# msp_mcu.net
KiCad netlist of a schematic drawn in Altium Designer
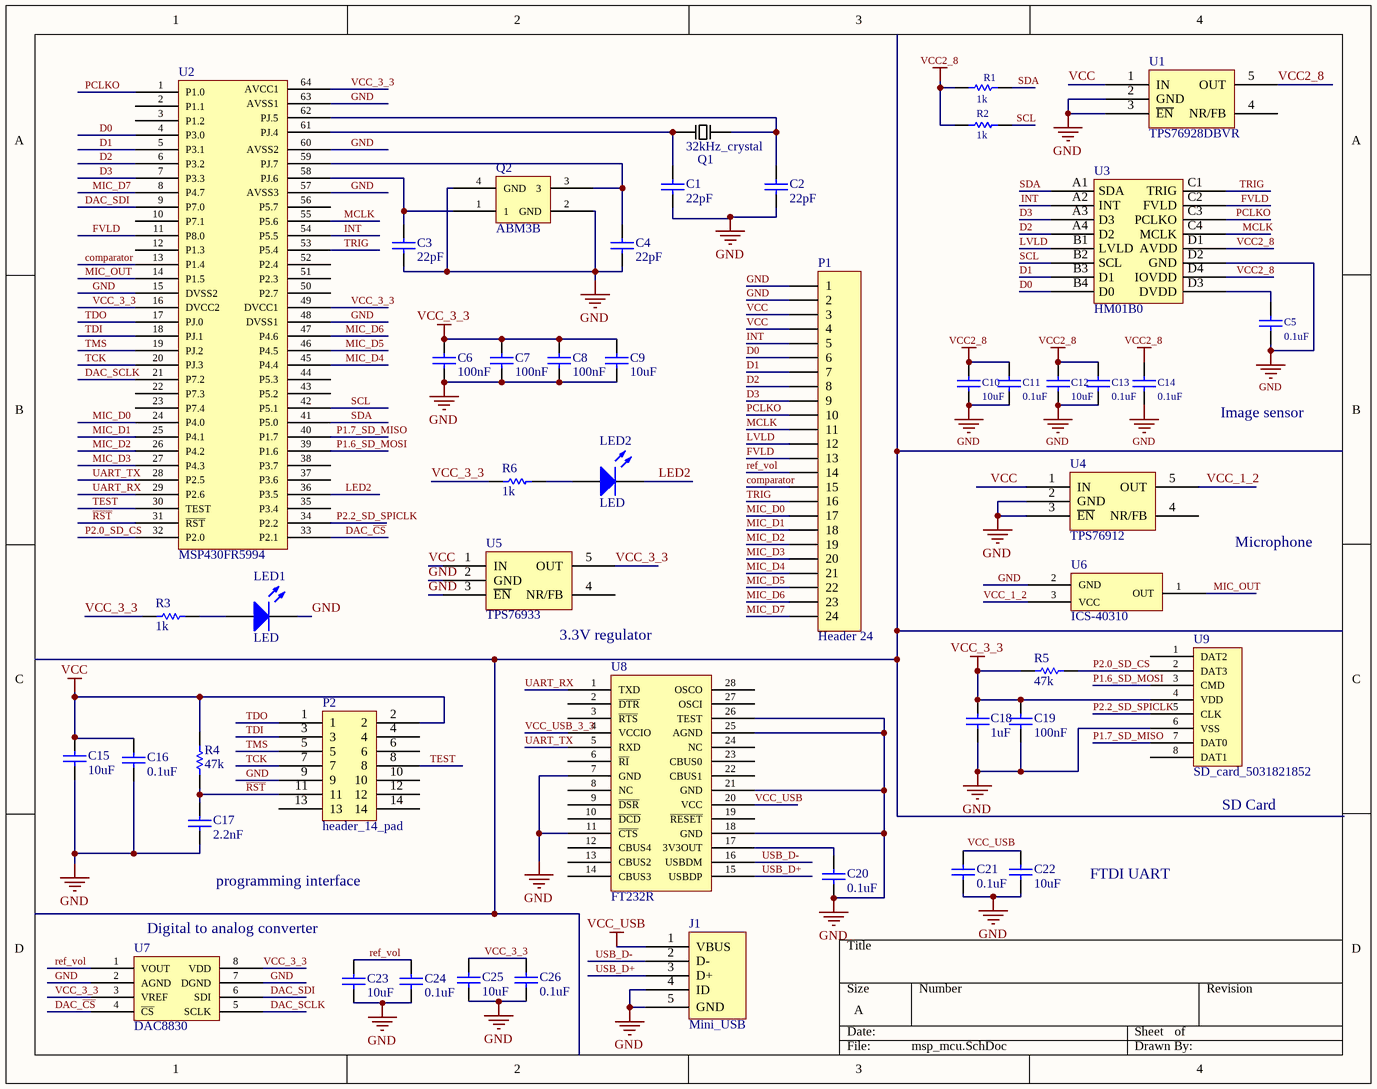
[diagram p0: msp_mcu.SchDoc]

(export (version "E")
  (design (tool "Eeschema 10.0.6"))
  (components
    (comp (ref "C1")
      (value "22pF")
      (footprint "0603")
      (description "Ceramic Capacitor (Surface Mount)")
      (fields (field (name "MANUFACTURER") "Generic Ceramic Chip Cap (TBD)") (field (name "Comment") "Cap"))
      (libsource (lib "wisp") (part "Cap"))
    )
    (comp (ref "C2")
      (value "22pF")
      (footprint "0603")
      (description "Ceramic Capacitor (Surface Mount)")
      (fields (field (name "MANUFACTURER") "Generic Ceramic Chip Cap (TBD)") (field (name "Comment") "Cap"))
      (libsource (lib "wisp") (part "Cap"))
    )
    (comp (ref "C3")
      (value "22pF")
      (footprint "0603")
      (description "Ceramic Capacitor (Surface Mount)")
      (fields (field (name "MANUFACTURER") "Generic Ceramic Chip Cap (TBD)") (field (name "Comment") "Cap"))
      (libsource (lib "wisp") (part "Cap"))
    )
    (comp (ref "C4")
      (value "22pF")
      (footprint "0603")
      (description "Ceramic Capacitor (Surface Mount)")
      (fields (field (name "MANUFACTURER") "Generic Ceramic Chip Cap (TBD)") (field (name "Comment") "Cap"))
      (libsource (lib "wisp") (part "Cap"))
    )
    (comp (ref "C5")
      (value "0.1uF")
      (footprint "0603")
      (description "Ceramic Capacitor (Surface Mount)")
      (fields (field (name "MANUFACTURER") "Generic Ceramic Chip Cap (TBD)") (field (name "Comment") "Cap"))
      (libsource (lib "wisp") (part "Cap"))
    )
    (comp (ref "C6")
      (value "100nF")
      (footprint "0603")
      (description "Ceramic Capacitor (Surface Mount)")
      (fields (field (name "MANUFACTURER") "Generic Ceramic Chip Cap (TBD)") (field (name "Comment") "Cap"))
      (libsource (lib "wisp") (part "Cap"))
    )
    (comp (ref "C7")
      (value "100nF")
      (footprint "0603")
      (description "Ceramic Capacitor (Surface Mount)")
      (fields (field (name "MANUFACTURER") "Generic Ceramic Chip Cap (TBD)") (field (name "Comment") "Cap"))
      (libsource (lib "wisp") (part "Cap"))
    )
    (comp (ref "C8")
      (value "100nF")
      (footprint "0603")
      (description "Ceramic Capacitor (Surface Mount)")
      (fields (field (name "MANUFACTURER") "Generic Ceramic Chip Cap (TBD)") (field (name "Comment") "Cap"))
      (libsource (lib "wisp") (part "Cap"))
    )
    (comp (ref "C9")
      (value "10uF")
      (footprint "0603")
      (description "Ceramic Capacitor (Surface Mount)")
      (fields (field (name "MANUFACTURER") "Generic Ceramic Chip Cap (TBD)") (field (name "Comment") "Cap"))
      (libsource (lib "wisp") (part "Cap"))
    )
    (comp (ref "C10")
      (value "10uF")
      (footprint "0603")
      (description "Ceramic Capacitor (Surface Mount)")
      (fields (field (name "MANUFACTURER") "Generic Ceramic Chip Cap (TBD)") (field (name "Comment") "Cap"))
      (libsource (lib "wisp") (part "Cap"))
    )
    (comp (ref "C11")
      (value "0.1uF")
      (footprint "0603")
      (description "Ceramic Capacitor (Surface Mount)")
      (fields (field (name "MANUFACTURER") "Generic Ceramic Chip Cap (TBD)") (field (name "Comment") "Cap"))
      (libsource (lib "wisp") (part "Cap"))
    )
    (comp (ref "C12")
      (value "10uF")
      (footprint "0603")
      (description "Ceramic Capacitor (Surface Mount)")
      (fields (field (name "MANUFACTURER") "Generic Ceramic Chip Cap (TBD)") (field (name "Comment") "Cap"))
      (libsource (lib "wisp") (part "Cap"))
    )
    (comp (ref "C13")
      (value "0.1uF")
      (footprint "0603")
      (description "Ceramic Capacitor (Surface Mount)")
      (fields (field (name "MANUFACTURER") "Generic Ceramic Chip Cap (TBD)") (field (name "Comment") "Cap"))
      (libsource (lib "wisp") (part "Cap"))
    )
    (comp (ref "C14")
      (value "0.1uF")
      (footprint "0603")
      (description "Ceramic Capacitor (Surface Mount)")
      (fields (field (name "MANUFACTURER") "Generic Ceramic Chip Cap (TBD)") (field (name "Comment") "Cap"))
      (libsource (lib "wisp") (part "Cap"))
    )
    (comp (ref "C15")
      (value "10uF")
      (footprint "0603")
      (description "Ceramic Capacitor (Surface Mount)")
      (fields (field (name "MANUFACTURER") "Generic Ceramic Chip Cap (TBD)") (field (name "Comment") "Cap"))
      (libsource (lib "wisp") (part "Cap"))
    )
    (comp (ref "C16")
      (value "0.1uF")
      (footprint "0603")
      (description "Ceramic Capacitor (Surface Mount)")
      (fields (field (name "MANUFACTURER") "Generic Ceramic Chip Cap (TBD)") (field (name "Comment") "Cap"))
      (libsource (lib "wisp") (part "Cap"))
    )
    (comp (ref "C17")
      (value "2.2nF")
      (footprint "0603")
      (description "Ceramic Capacitor (Surface Mount)")
      (fields (field (name "MANUFACTURER") "Generic Ceramic Chip Cap (TBD)") (field (name "Comment") "Cap"))
      (libsource (lib "wisp") (part "Cap"))
    )
    (comp (ref "C18")
      (value "1uF")
      (footprint "0603")
      (description "Ceramic Capacitor (Surface Mount)")
      (fields (field (name "MANUFACTURER") "Generic Ceramic Chip Cap (TBD)") (field (name "Comment") "Cap"))
      (libsource (lib "wisp") (part "Cap"))
    )
    (comp (ref "C19")
      (value "100nF")
      (footprint "0603")
      (description "Ceramic Capacitor (Surface Mount)")
      (fields (field (name "MANUFACTURER") "Generic Ceramic Chip Cap (TBD)") (field (name "Comment") "Cap"))
      (libsource (lib "wisp") (part "Cap"))
    )
    (comp (ref "C20")
      (value "0.1uF")
      (footprint "0603")
      (description "Ceramic Capacitor (Surface Mount)")
      (fields (field (name "MANUFACTURER") "Generic Ceramic Chip Cap (TBD)") (field (name "Comment") "Cap"))
      (libsource (lib "wisp") (part "Cap"))
    )
    (comp (ref "C21")
      (value "0.1uF")
      (footprint "0603")
      (description "Ceramic Capacitor (Surface Mount)")
      (fields (field (name "MANUFACTURER") "Generic Ceramic Chip Cap (TBD)") (field (name "Comment") "Cap"))
      (libsource (lib "wisp") (part "Cap"))
    )
    (comp (ref "C22")
      (value "10uF")
      (footprint "0603")
      (description "Ceramic Capacitor (Surface Mount)")
      (fields (field (name "MANUFACTURER") "Generic Ceramic Chip Cap (TBD)") (field (name "Comment") "Cap"))
      (libsource (lib "wisp") (part "Cap"))
    )
    (comp (ref "C23")
      (value "10uF")
      (footprint "0603")
      (description "Ceramic Capacitor (Surface Mount)")
      (fields (field (name "MANUFACTURER") "Generic Ceramic Chip Cap (TBD)") (field (name "Comment") "Cap"))
      (libsource (lib "wisp") (part "Cap"))
    )
    (comp (ref "C24")
      (value "0.1uF")
      (footprint "0603")
      (description "Ceramic Capacitor (Surface Mount)")
      (fields (field (name "MANUFACTURER") "Generic Ceramic Chip Cap (TBD)") (field (name "Comment") "Cap"))
      (libsource (lib "wisp") (part "Cap"))
    )
    (comp (ref "C25")
      (value "10uF")
      (footprint "0603")
      (description "Ceramic Capacitor (Surface Mount)")
      (fields (field (name "MANUFACTURER") "Generic Ceramic Chip Cap (TBD)") (field (name "Comment") "Cap"))
      (libsource (lib "wisp") (part "Cap"))
    )
    (comp (ref "C26")
      (value "0.1uF")
      (footprint "0603")
      (description "Ceramic Capacitor (Surface Mount)")
      (fields (field (name "MANUFACTURER") "Generic Ceramic Chip Cap (TBD)") (field (name "Comment") "Cap"))
      (libsource (lib "wisp") (part "Cap"))
    )
    (comp (ref "J1")
      (value "Mini_USB")
      (footprint "Mini_USB")
      (libsource (lib "pengyulib") (part "Mini_USB"))
    )
    (comp (ref "LED1") (value "LED") (libsource (lib "pengyulib") (part "LED")))
    (comp (ref "LED2") (value "LED") (libsource (lib "pengyulib") (part "LED")))
    (comp (ref "P1")
      (value "Header 24")
      (footprint "HDR1X24")
      (description "Header, 24-Pin")
      (fields (field (name "PUBLISHER") "Altium Limited"))
      (libsource (lib "Miscellaneous Connectors") (part "Header 24"))
    )
    (comp (ref "P2")
      (value "header_14_pad")
      (footprint "header_14_pad")
      (libsource (lib "pengyulib") (part "header_14_pad"))
    )
    (comp (ref "Q1")
      (value "32kHz_crystal")
      (footprint "32kHz_crystal")
      (libsource (lib "pengyulib") (part "32kHz_crystal"))
    )
    (comp (ref "Q2") (value "ABM3B") (footprint "ABM3B") (libsource (lib "pengyulib") (part "ABM3B")))
    (comp (ref "R1")
      (value "1k")
      (footprint "0603")
      (description "Chip Resistor (Surface Mount)")
      (fields (field (name "MANUFACTURER") "Generic Chip Res (TBD)") (field (name "Comment") "Res"))
      (libsource (lib "wisp") (part "Res"))
    )
    (comp (ref "R2")
      (value "1k")
      (footprint "0603")
      (description "Chip Resistor (Surface Mount)")
      (fields (field (name "MANUFACTURER") "Generic Chip Res (TBD)") (field (name "Comment") "Res"))
      (libsource (lib "wisp") (part "Res"))
    )
    (comp (ref "R3")
      (value "1k")
      (footprint "0603")
      (description "Chip Resistor (Surface Mount)")
      (fields (field (name "MANUFACTURER") "Generic Chip Res (TBD)") (field (name "Comment") "Res"))
      (libsource (lib "wisp") (part "Res"))
    )
    (comp (ref "R4")
      (value "47k")
      (footprint "0603")
      (description "Chip Resistor (Surface Mount)")
      (fields (field (name "MANUFACTURER") "Generic Chip Res (TBD)") (field (name "Comment") "Res"))
      (libsource (lib "wisp") (part "Res"))
    )
    (comp (ref "R5")
      (value "47k")
      (footprint "0603")
      (description "Chip Resistor (Surface Mount)")
      (fields (field (name "MANUFACTURER") "Generic Chip Res (TBD)") (field (name "Comment") "Res"))
      (libsource (lib "wisp") (part "Res"))
    )
    (comp (ref "R6")
      (value "1k")
      (footprint "0603")
      (description "Chip Resistor (Surface Mount)")
      (fields (field (name "MANUFACTURER") "Generic Chip Res (TBD)") (field (name "Comment") "Res"))
      (libsource (lib "wisp") (part "Res"))
    )
    (comp (ref "U1")
      (value "TPS76928DBVR")
      (footprint "TPS73633")
      (description "TPS73633")
      (libsource (lib "pengyulib") (part "TPS76928DBVR"))
    )
    (comp (ref "U2")
      (value "MSP430FR5994")
      (footprint "MSP430FR5994")
      (libsource (lib "pengyulib") (part "MSP430FR5994"))
    )
    (comp (ref "U3") (value "HM01B0") (footprint "HM01B0") (libsource (lib "pengyulib") (part "HM01B0")))
    (comp (ref "U4")
      (value "TPS76912")
      (footprint "TPS73633")
      (description "TPS73633")
      (libsource (lib "pengyulib") (part "TPS76912"))
    )
    (comp (ref "U5")
      (value "TPS76933")
      (footprint "TPS73633")
      (description "TPS73633")
      (libsource (lib "pengyulib") (part "TPS76933"))
    )
    (comp (ref "U6")
      (value "ICS-40310")
      (footprint "ICS-40310")
      (libsource (lib "pengyulib") (part "ICS-40310"))
    )
    (comp (ref "U7") (value "DAC8830") (footprint "DAC8830") (libsource (lib "pengyulib") (part "DAC8830")))
    (comp (ref "U8") (value "FT232R") (footprint "FT232R") (libsource (lib "pengyulib") (part "FT232R")))
    (comp (ref "U9")
      (value "SD_card_5031821852")
      (footprint "SD_card_5031821852")
      (libsource (lib "pengyulib") (part "SD_card_5031821852"))
    )
  )
  (nets
    (net (code "1") (name "/D0") (class "Default")
      (node (ref "P1") (pin "6") (pinfunction "6_6") (pintype "passive"))
      (node (ref "U2") (pin "4") (pinfunction "P3.0_4") (pintype "passive"))
      (node (ref "U3") (pin "B4") (pinfunction "D0_B4") (pintype "passive"))
    )
    (net (code "2") (name "/D1") (class "Default")
      (node (ref "P1") (pin "7") (pinfunction "7_7") (pintype "passive"))
      (node (ref "U2") (pin "5") (pinfunction "P3.1_5") (pintype "passive"))
      (node (ref "U3") (pin "B3") (pinfunction "D1_B3") (pintype "passive"))
    )
    (net (code "3") (name "/D2") (class "Default")
      (node (ref "P1") (pin "8") (pinfunction "8_8") (pintype "passive"))
      (node (ref "U2") (pin "6") (pinfunction "P3.2_6") (pintype "passive"))
      (node (ref "U3") (pin "A4") (pinfunction "D2_A4") (pintype "passive"))
    )
    (net (code "4") (name "/D3") (class "Default")
      (node (ref "P1") (pin "9") (pinfunction "9_9") (pintype "passive"))
      (node (ref "U2") (pin "7") (pinfunction "P3.3_7") (pintype "passive"))
      (node (ref "U3") (pin "A3") (pinfunction "D3_A3") (pintype "passive"))
    )
    (net (code "5") (name "/DAC_SCLK") (class "Default")
      (node (ref "U2") (pin "21") (pinfunction "P7.2_21") (pintype "passive"))
      (node (ref "U7") (pin "5") (pinfunction "SCLK_5") (pintype "passive"))
    )
    (net (code "6") (name "/DAC_SDI") (class "Default")
      (node (ref "U2") (pin "9") (pinfunction "P7.0_9") (pintype "passive"))
      (node (ref "U7") (pin "6") (pinfunction "SDI_6") (pintype "passive"))
    )
    (net (code "7") (name "/DAC_~{CS}") (class "Default")
      (node (ref "U2") (pin "33") (pinfunction "P2.1_33") (pintype "passive"))
      (node (ref "U7") (pin "4") (pinfunction "~{CS}_4") (pintype "passive"))
    )
    (net (code "8") (name "/FVLD") (class "Default")
      (node (ref "P1") (pin "13") (pinfunction "13_13") (pintype "passive"))
      (node (ref "U2") (pin "11") (pinfunction "P8.0_11") (pintype "passive"))
      (node (ref "U3") (pin "C2") (pinfunction "FVLD_C2") (pintype "passive"))
    )
    (net (code "9") (name "/INT") (class "Default")
      (node (ref "P1") (pin "5") (pinfunction "5_5") (pintype "passive"))
      (node (ref "U2") (pin "54") (pinfunction "P5.5_54") (pintype "passive"))
      (node (ref "U3") (pin "A2") (pinfunction "INT_A2") (pintype "passive"))
    )
    (net (code "10") (name "/LED2") (class "Default")
      (node (ref "LED2") (pin "2") (pinfunction "K_2") (pintype "passive"))
      (node (ref "U2") (pin "36") (pinfunction "P3.5_36") (pintype "passive"))
    )
    (net (code "11") (name "/LVLD") (class "Default")
      (node (ref "P1") (pin "12") (pinfunction "12_12") (pintype "passive"))
      (node (ref "U3") (pin "B1") (pinfunction "LVLD_B1") (pintype "passive"))
    )
    (net (code "12") (name "/MCLK") (class "Default")
      (node (ref "P1") (pin "11") (pinfunction "11_11") (pintype "passive"))
      (node (ref "U2") (pin "55") (pinfunction "P5.6_55") (pintype "passive"))
      (node (ref "U3") (pin "C4") (pinfunction "MCLK_C4") (pintype "passive"))
    )
    (net (code "13") (name "/MIC_D0") (class "Default")
      (node (ref "P1") (pin "17") (pinfunction "17_17") (pintype "passive"))
      (node (ref "U2") (pin "24") (pinfunction "P4.0_24") (pintype "passive"))
    )
    (net (code "14") (name "/MIC_D1") (class "Default")
      (node (ref "P1") (pin "18") (pinfunction "18_18") (pintype "passive"))
      (node (ref "U2") (pin "25") (pinfunction "P4.1_25") (pintype "passive"))
    )
    (net (code "15") (name "/MIC_D2") (class "Default")
      (node (ref "P1") (pin "19") (pinfunction "19_19") (pintype "passive"))
      (node (ref "U2") (pin "26") (pinfunction "P4.2_26") (pintype "passive"))
    )
    (net (code "16") (name "/MIC_D3") (class "Default")
      (node (ref "P1") (pin "20") (pinfunction "20_20") (pintype "passive"))
      (node (ref "U2") (pin "27") (pinfunction "P4.3_27") (pintype "passive"))
    )
    (net (code "17") (name "/MIC_D4") (class "Default")
      (node (ref "P1") (pin "21") (pinfunction "21_21") (pintype "passive"))
      (node (ref "U2") (pin "45") (pinfunction "P4.4_45") (pintype "passive"))
    )
    (net (code "18") (name "/MIC_D5") (class "Default")
      (node (ref "P1") (pin "22") (pinfunction "22_22") (pintype "passive"))
      (node (ref "U2") (pin "46") (pinfunction "P4.5_46") (pintype "passive"))
    )
    (net (code "19") (name "/MIC_D6") (class "Default")
      (node (ref "P1") (pin "23") (pinfunction "23_23") (pintype "passive"))
      (node (ref "U2") (pin "47") (pinfunction "P4.6_47") (pintype "passive"))
    )
    (net (code "20") (name "/MIC_D7") (class "Default")
      (node (ref "P1") (pin "24") (pinfunction "24_24") (pintype "passive"))
      (node (ref "U2") (pin "8") (pinfunction "P4.7_8") (pintype "passive"))
    )
    (net (code "21") (name "/MIC_OUT") (class "Default")
      (node (ref "U2") (pin "14") (pinfunction "P1.5_14") (pintype "passive"))
      (node (ref "U6") (pin "1") (pinfunction "OUT_1") (pintype "passive"))
    )
    (net (code "22") (name "/P1.6_SD_MOSI") (class "Default")
      (node (ref "U2") (pin "39") (pinfunction "P1.6_39") (pintype "passive"))
      (node (ref "U9") (pin "3") (pinfunction "CMD_3") (pintype "passive"))
    )
    (net (code "23") (name "/P1.7_SD_MISO") (class "Default")
      (node (ref "U2") (pin "40") (pinfunction "P1.7_40") (pintype "passive"))
      (node (ref "U9") (pin "7") (pinfunction "DAT0_7") (pintype "passive"))
    )
    (net (code "24") (name "/P2.0_SD_CS") (class "Default")
      (node (ref "R5") (pin "2") (pinfunction "2_2") (pintype "passive"))
      (node (ref "U2") (pin "32") (pinfunction "P2.0_32") (pintype "passive"))
      (node (ref "U9") (pin "2") (pinfunction "DAT3_2") (pintype "passive"))
    )
    (net (code "25") (name "/P2.2_SD_SPICLK") (class "Default")
      (node (ref "U2") (pin "34") (pinfunction "P2.2_34") (pintype "passive"))
      (node (ref "U9") (pin "5") (pinfunction "CLK_5") (pintype "passive"))
    )
    (net (code "26") (name "/PCLKO") (class "Default")
      (node (ref "P1") (pin "10") (pinfunction "10_10") (pintype "passive"))
      (node (ref "U2") (pin "1") (pinfunction "P1.0_1") (pintype "passive"))
      (node (ref "U3") (pin "C3") (pinfunction "PCLKO_C3") (pintype "passive"))
    )
    (net (code "27") (name "/SCL") (class "Default")
      (node (ref "R2") (pin "1") (pinfunction "1_1") (pintype "passive"))
      (node (ref "U2") (pin "42") (pinfunction "P5.1_42") (pintype "passive"))
      (node (ref "U3") (pin "B2") (pinfunction "SCL_B2") (pintype "passive"))
    )
    (net (code "28") (name "/SDA") (class "Default")
      (node (ref "R1") (pin "1") (pinfunction "1_1") (pintype "passive"))
      (node (ref "U2") (pin "41") (pinfunction "P5.0_41") (pintype "passive"))
      (node (ref "U3") (pin "A1") (pinfunction "SDA_A1") (pintype "passive"))
    )
    (net (code "29") (name "/TCK") (class "Default")
      (node (ref "P2") (pin "7") (pinfunction "7_7") (pintype "passive"))
      (node (ref "U2") (pin "20") (pinfunction "PJ.3_20") (pintype "passive"))
    )
    (net (code "30") (name "/TDI") (class "Default")
      (node (ref "P2") (pin "3") (pinfunction "3_3") (pintype "passive"))
      (node (ref "U2") (pin "18") (pinfunction "PJ.1_18") (pintype "passive"))
    )
    (net (code "31") (name "/TDO") (class "Default")
      (node (ref "P2") (pin "1") (pinfunction "1_1") (pintype "passive"))
      (node (ref "U2") (pin "17") (pinfunction "PJ.0_17") (pintype "passive"))
    )
    (net (code "32") (name "/TEST") (class "Default")
      (node (ref "P2") (pin "8") (pinfunction "8_8") (pintype "passive"))
      (node (ref "U2") (pin "30") (pinfunction "TEST_30") (pintype "passive"))
    )
    (net (code "33") (name "/TMS") (class "Default")
      (node (ref "P2") (pin "5") (pinfunction "5_5") (pintype "passive"))
      (node (ref "U2") (pin "19") (pinfunction "PJ.2_19") (pintype "passive"))
    )
    (net (code "34") (name "/TRIG") (class "Default")
      (node (ref "P1") (pin "16") (pinfunction "16_16") (pintype "passive"))
      (node (ref "U2") (pin "53") (pinfunction "P5.4_53") (pintype "passive"))
      (node (ref "U3") (pin "C1") (pinfunction "TRIG_C1") (pintype "passive"))
    )
    (net (code "35") (name "/UART_RX") (class "Default")
      (node (ref "U2") (pin "29") (pinfunction "P2.6_29") (pintype "passive"))
      (node (ref "U8") (pin "1") (pinfunction "TXD_1") (pintype "passive"))
    )
    (net (code "36") (name "/UART_TX") (class "Default")
      (node (ref "U2") (pin "28") (pinfunction "P2.5_28") (pintype "passive"))
      (node (ref "U8") (pin "5") (pinfunction "RXD_5") (pintype "passive"))
    )
    (net (code "37") (name "/USB_D+") (class "Default")
      (node (ref "J1") (pin "3") (pinfunction "D+_3") (pintype "passive"))
      (node (ref "U8") (pin "15") (pinfunction "USBDP_15") (pintype "passive"))
    )
    (net (code "38") (name "/USB_D-") (class "Default")
      (node (ref "J1") (pin "2") (pinfunction "D-_2") (pintype "passive"))
      (node (ref "U8") (pin "16") (pinfunction "USBDM_16") (pintype "passive"))
    )
    (net (code "39") (name "/VCC_1_2") (class "Default")
      (node (ref "U4") (pin "5") (pinfunction "OUT_5") (pintype "passive"))
      (node (ref "U6") (pin "3") (pinfunction "VCC_3") (pintype "passive"))
    )
    (net (code "40") (name "/VCC_USB_3_3") (class "Default")
      (node (ref "U8") (pin "4") (pinfunction "VCCIO_4") (pintype "passive"))
    )
    (net (code "41") (name "/comparator") (class "Default")
      (node (ref "P1") (pin "15") (pinfunction "15_15") (pintype "passive"))
      (node (ref "U2") (pin "13") (pinfunction "P1.4_13") (pintype "passive"))
    )
    (net (code "42") (name "/ref_vol") (class "Default")
      (node (ref "C23") (pin "2") (pinfunction "2_2") (pintype "passive"))
      (node (ref "C24") (pin "2") (pinfunction "2_2") (pintype "passive"))
      (node (ref "P1") (pin "14") (pinfunction "14_14") (pintype "passive"))
      (node (ref "U7") (pin "1") (pinfunction "VOUT_1") (pintype "passive"))
    )
    (net (code "43") (name "/~{RST}") (class "Default")
      (node (ref "C17") (pin "2") (pinfunction "2_2") (pintype "passive"))
      (node (ref "P2") (pin "11") (pinfunction "11_11") (pintype "passive"))
      (node (ref "R4") (pin "1") (pinfunction "1_1") (pintype "passive"))
      (node (ref "U2") (pin "31") (pinfunction "~{RST}_31") (pintype "passive"))
    )
    (net (code "44") (name "GND") (class "Default")
      (node (ref "C1") (pin "1") (pinfunction "1_1") (pintype "passive"))
      (node (ref "C10") (pin "1") (pinfunction "1_1") (pintype "passive"))
      (node (ref "C11") (pin "1") (pinfunction "1_1") (pintype "passive"))
      (node (ref "C12") (pin "1") (pinfunction "1_1") (pintype "passive"))
      (node (ref "C13") (pin "1") (pinfunction "1_1") (pintype "passive"))
      (node (ref "C14") (pin "1") (pinfunction "1_1") (pintype "passive"))
      (node (ref "C15") (pin "1") (pinfunction "1_1") (pintype "passive"))
      (node (ref "C16") (pin "1") (pinfunction "1_1") (pintype "passive"))
      (node (ref "C17") (pin "1") (pinfunction "1_1") (pintype "passive"))
      (node (ref "C18") (pin "1") (pinfunction "1_1") (pintype "passive"))
      (node (ref "C19") (pin "1") (pinfunction "1_1") (pintype "passive"))
      (node (ref "C2") (pin "1") (pinfunction "1_1") (pintype "passive"))
      (node (ref "C20") (pin "2") (pinfunction "2_2") (pintype "passive"))
      (node (ref "C21") (pin "1") (pinfunction "1_1") (pintype "passive"))
      (node (ref "C22") (pin "1") (pinfunction "1_1") (pintype "passive"))
      (node (ref "C23") (pin "1") (pinfunction "1_1") (pintype "passive"))
      (node (ref "C24") (pin "1") (pinfunction "1_1") (pintype "passive"))
      (node (ref "C25") (pin "1") (pinfunction "1_1") (pintype "passive"))
      (node (ref "C26") (pin "1") (pinfunction "1_1") (pintype "passive"))
      (node (ref "C3") (pin "1") (pinfunction "1_1") (pintype "passive"))
      (node (ref "C4") (pin "1") (pinfunction "1_1") (pintype "passive"))
      (node (ref "C5") (pin "1") (pinfunction "1_1") (pintype "passive"))
      (node (ref "C6") (pin "1") (pinfunction "1_1") (pintype "passive"))
      (node (ref "C7") (pin "1") (pinfunction "1_1") (pintype "passive"))
      (node (ref "C8") (pin "1") (pinfunction "1_1") (pintype "passive"))
      (node (ref "C9") (pin "1") (pinfunction "1_1") (pintype "passive"))
      (node (ref "J1") (pin "4") (pinfunction "ID_4") (pintype "passive"))
      (node (ref "J1") (pin "5") (pinfunction "GND_5") (pintype "passive"))
      (node (ref "LED1") (pin "2") (pinfunction "K_2") (pintype "passive"))
      (node (ref "P1") (pin "1") (pinfunction "1_1") (pintype "passive"))
      (node (ref "P1") (pin "2") (pinfunction "2_2") (pintype "passive"))
      (node (ref "P2") (pin "9") (pinfunction "9_9") (pintype "passive"))
      (node (ref "Q2") (pin "2") (pinfunction "GND_2") (pintype "passive"))
      (node (ref "Q2") (pin "4") (pinfunction "GND_4") (pintype "passive"))
      (node (ref "U1") (pin "2") (pinfunction "GND_2") (pintype "passive"))
      (node (ref "U1") (pin "3") (pinfunction "~{EN}_3") (pintype "passive"))
      (node (ref "U2") (pin "15") (pinfunction "DVSS2_15") (pintype "passive"))
      (node (ref "U2") (pin "48") (pinfunction "DVSS1_48") (pintype "passive"))
      (node (ref "U2") (pin "57") (pinfunction "AVSS3_57") (pintype "passive"))
      (node (ref "U2") (pin "60") (pinfunction "AVSS2_60") (pintype "passive"))
      (node (ref "U2") (pin "63") (pinfunction "AVSS1_63") (pintype "passive"))
      (node (ref "U3") (pin "D2") (pinfunction "GND_D2") (pintype "passive"))
      (node (ref "U4") (pin "2") (pinfunction "GND_2") (pintype "passive"))
      (node (ref "U4") (pin "3") (pinfunction "~{EN}_3") (pintype "passive"))
      (node (ref "U5") (pin "2") (pinfunction "GND_2") (pintype "passive"))
      (node (ref "U5") (pin "3") (pinfunction "~{EN}_3") (pintype "passive"))
      (node (ref "U6") (pin "2") (pinfunction "GND_2") (pintype "passive"))
      (node (ref "U7") (pin "2") (pinfunction "AGND_2") (pintype "passive"))
      (node (ref "U7") (pin "7") (pinfunction "DGND_7") (pintype "passive"))
      (node (ref "U8") (pin "11") (pinfunction "~{CTS}_11") (pintype "passive"))
      (node (ref "U8") (pin "18") (pinfunction "GND_18") (pintype "passive"))
      (node (ref "U8") (pin "21") (pinfunction "GND_21") (pintype "passive"))
      (node (ref "U8") (pin "25") (pinfunction "AGND_25") (pintype "passive"))
      (node (ref "U8") (pin "26") (pinfunction "TEST_26") (pintype "passive"))
      (node (ref "U8") (pin "7") (pinfunction "GND_7") (pintype "passive"))
      (node (ref "U9") (pin "6") (pinfunction "VSS_6") (pintype "passive"))
    )
    (net (code "45") (name "Net-(C21-Pad2)") (class "Default")
      (node (ref "C21") (pin "2") (pinfunction "2_2") (pintype "passive"))
      (node (ref "C22") (pin "2") (pinfunction "2_2") (pintype "passive"))
    )
    (net (code "46") (name "Net-(LED1-A)") (class "Default")
      (node (ref "LED1") (pin "1") (pinfunction "A_1") (pintype "passive"))
      (node (ref "R3") (pin "1") (pinfunction "1_1") (pintype "passive"))
    )
    (net (code "47") (name "Net-(LED2-A)") (class "Default")
      (node (ref "LED2") (pin "1") (pinfunction "A_1") (pintype "passive"))
      (node (ref "R6") (pin "1") (pinfunction "1_1") (pintype "passive"))
    )
    (net (code "48") (name "Net-(U2-PJ.4)") (class "Default")
      (node (ref "C1") (pin "2") (pinfunction "2_2") (pintype "passive"))
      (node (ref "Q1") (pin "2") (pinfunction "2_2") (pintype "power_in"))
      (node (ref "U2") (pin "61") (pinfunction "PJ.4_61") (pintype "passive"))
    )
    (net (code "49") (name "Net-(U2-PJ.5)") (class "Default")
      (node (ref "C2") (pin "2") (pinfunction "2_2") (pintype "passive"))
      (node (ref "Q1") (pin "1") (pinfunction "1_1") (pintype "power_in"))
      (node (ref "U2") (pin "62") (pinfunction "PJ.5_62") (pintype "passive"))
    )
    (net (code "50") (name "Net-(U2-PJ.6)") (class "Default")
      (node (ref "C3") (pin "2") (pinfunction "2_2") (pintype "passive"))
      (node (ref "Q2") (pin "1") (pinfunction "1_1") (pintype "passive"))
      (node (ref "U2") (pin "58") (pinfunction "PJ.6_58") (pintype "passive"))
    )
    (net (code "51") (name "Net-(U2-PJ.7)") (class "Default")
      (node (ref "C4") (pin "2") (pinfunction "2_2") (pintype "passive"))
      (node (ref "Q2") (pin "3") (pinfunction "3_3") (pintype "passive"))
      (node (ref "U2") (pin "59") (pinfunction "PJ.7_59") (pintype "passive"))
    )
    (net (code "52") (name "Net-(U3-DVDD)") (class "Default")
      (node (ref "C5") (pin "2") (pinfunction "2_2") (pintype "passive"))
      (node (ref "U3") (pin "D3") (pinfunction "DVDD_D3") (pintype "passive"))
    )
    (net (code "53") (name "Net-(U8-3V3OUT)") (class "Default")
      (node (ref "C20") (pin "1") (pinfunction "1_1") (pintype "passive"))
      (node (ref "U8") (pin "17") (pinfunction "3V3OUT_17") (pintype "passive"))
    )
    (net (code "54") (name "VCC") (class "Default")
      (node (ref "C15") (pin "2") (pinfunction "2_2") (pintype "passive"))
      (node (ref "C16") (pin "2") (pinfunction "2_2") (pintype "passive"))
      (node (ref "P1") (pin "3") (pinfunction "3_3") (pintype "passive"))
      (node (ref "P1") (pin "4") (pinfunction "4_4") (pintype "passive"))
      (node (ref "P2") (pin "2") (pinfunction "2_2") (pintype "passive"))
      (node (ref "R4") (pin "2") (pinfunction "2_2") (pintype "passive"))
      (node (ref "U1") (pin "1") (pinfunction "IN_1") (pintype "passive"))
      (node (ref "U4") (pin "1") (pinfunction "IN_1") (pintype "passive"))
      (node (ref "U5") (pin "1") (pinfunction "IN_1") (pintype "passive"))
    )
    (net (code "55") (name "VCC2_8") (class "Default")
      (node (ref "C10") (pin "2") (pinfunction "2_2") (pintype "passive"))
      (node (ref "C11") (pin "2") (pinfunction "2_2") (pintype "passive"))
      (node (ref "C12") (pin "2") (pinfunction "2_2") (pintype "passive"))
      (node (ref "C13") (pin "2") (pinfunction "2_2") (pintype "passive"))
      (node (ref "C14") (pin "2") (pinfunction "2_2") (pintype "passive"))
      (node (ref "R1") (pin "2") (pinfunction "2_2") (pintype "passive"))
      (node (ref "R2") (pin "2") (pinfunction "2_2") (pintype "passive"))
      (node (ref "U1") (pin "5") (pinfunction "OUT_5") (pintype "passive"))
      (node (ref "U3") (pin "D1") (pinfunction "AVDD_D1") (pintype "passive"))
      (node (ref "U3") (pin "D4") (pinfunction "IOVDD_D4") (pintype "passive"))
    )
    (net (code "56") (name "VCC_3_3") (class "Default")
      (node (ref "C18") (pin "2") (pinfunction "2_2") (pintype "passive"))
      (node (ref "C19") (pin "2") (pinfunction "2_2") (pintype "passive"))
      (node (ref "C25") (pin "2") (pinfunction "2_2") (pintype "passive"))
      (node (ref "C26") (pin "2") (pinfunction "2_2") (pintype "passive"))
      (node (ref "C6") (pin "2") (pinfunction "2_2") (pintype "passive"))
      (node (ref "C7") (pin "2") (pinfunction "2_2") (pintype "passive"))
      (node (ref "C8") (pin "2") (pinfunction "2_2") (pintype "passive"))
      (node (ref "C9") (pin "2") (pinfunction "2_2") (pintype "passive"))
      (node (ref "R3") (pin "2") (pinfunction "2_2") (pintype "passive"))
      (node (ref "R5") (pin "1") (pinfunction "1_1") (pintype "passive"))
      (node (ref "R6") (pin "2") (pinfunction "2_2") (pintype "passive"))
      (node (ref "U2") (pin "16") (pinfunction "DVCC2_16") (pintype "passive"))
      (node (ref "U2") (pin "49") (pinfunction "DVCC1_49") (pintype "passive"))
      (node (ref "U2") (pin "64") (pinfunction "AVCC1_64") (pintype "passive"))
      (node (ref "U5") (pin "5") (pinfunction "OUT_5") (pintype "passive"))
      (node (ref "U7") (pin "3") (pinfunction "VREF_3") (pintype "passive"))
      (node (ref "U7") (pin "8") (pinfunction "VDD_8") (pintype "passive"))
      (node (ref "U9") (pin "4") (pinfunction "VDD_4") (pintype "passive"))
    )
    (net (code "57") (name "VCC_USB") (class "Default")
      (node (ref "J1") (pin "1") (pinfunction "VBUS_1") (pintype "passive"))
      (node (ref "U8") (pin "20") (pinfunction "VCC_20") (pintype "passive"))
    )
    (net (code "58") (name "unconnected-(P2-Pad4)") (class "Default")
      (node (ref "P2") (pin "4") (pinfunction "4_4") (pintype "passive"))
    )
    (net (code "59") (name "unconnected-(P2-Pad6)") (class "Default")
      (node (ref "P2") (pin "6") (pinfunction "6_6") (pintype "passive"))
    )
    (net (code "60") (name "unconnected-(P2-Pad10)") (class "Default")
      (node (ref "P2") (pin "10") (pinfunction "10_10") (pintype "passive"))
    )
    (net (code "61") (name "unconnected-(P2-Pad12)") (class "Default")
      (node (ref "P2") (pin "12") (pinfunction "12_12") (pintype "passive"))
    )
    (net (code "62") (name "unconnected-(P2-Pad13)") (class "Default")
      (node (ref "P2") (pin "13") (pinfunction "13_13") (pintype "passive"))
    )
    (net (code "63") (name "unconnected-(P2-Pad14)") (class "Default")
      (node (ref "P2") (pin "14") (pinfunction "14_14") (pintype "passive"))
    )
    (net (code "64") (name "unconnected-(U1-NR{slash}FB-Pad4)") (class "Default")
      (node (ref "U1") (pin "4") (pinfunction "NR/FB_4") (pintype "passive"))
    )
    (net (code "65") (name "unconnected-(U2-P1.1-Pad2)") (class "Default")
      (node (ref "U2") (pin "2") (pinfunction "P1.1_2") (pintype "passive"))
    )
    (net (code "66") (name "unconnected-(U2-P1.2-Pad3)") (class "Default")
      (node (ref "U2") (pin "3") (pinfunction "P1.2_3") (pintype "passive"))
    )
    (net (code "67") (name "unconnected-(U2-P1.3-Pad12)") (class "Default")
      (node (ref "U2") (pin "12") (pinfunction "P1.3_12") (pintype "passive"))
    )
    (net (code "68") (name "unconnected-(U2-P2.3-Pad51)") (class "Default")
      (node (ref "U2") (pin "51") (pinfunction "P2.3_51") (pintype "passive"))
    )
    (net (code "69") (name "unconnected-(U2-P2.4-Pad52)") (class "Default")
      (node (ref "U2") (pin "52") (pinfunction "P2.4_52") (pintype "passive"))
    )
    (net (code "70") (name "unconnected-(U2-P2.7-Pad50)") (class "Default")
      (node (ref "U2") (pin "50") (pinfunction "P2.7_50") (pintype "passive"))
    )
    (net (code "71") (name "unconnected-(U2-P3.4-Pad35)") (class "Default")
      (node (ref "U2") (pin "35") (pinfunction "P3.4_35") (pintype "passive"))
    )
    (net (code "72") (name "unconnected-(U2-P3.6-Pad37)") (class "Default")
      (node (ref "U2") (pin "37") (pinfunction "P3.6_37") (pintype "passive"))
    )
    (net (code "73") (name "unconnected-(U2-P3.7-Pad38)") (class "Default")
      (node (ref "U2") (pin "38") (pinfunction "P3.7_38") (pintype "passive"))
    )
    (net (code "74") (name "unconnected-(U2-P5.2-Pad43)") (class "Default")
      (node (ref "U2") (pin "43") (pinfunction "P5.2_43") (pintype "passive"))
    )
    (net (code "75") (name "unconnected-(U2-P5.3-Pad44)") (class "Default")
      (node (ref "U2") (pin "44") (pinfunction "P5.3_44") (pintype "passive"))
    )
    (net (code "76") (name "unconnected-(U2-P5.7-Pad56)") (class "Default")
      (node (ref "U2") (pin "56") (pinfunction "P5.7_56") (pintype "passive"))
    )
    (net (code "77") (name "unconnected-(U2-P7.1-Pad10)") (class "Default")
      (node (ref "U2") (pin "10") (pinfunction "P7.1_10") (pintype "passive"))
    )
    (net (code "78") (name "unconnected-(U2-P7.3-Pad22)") (class "Default")
      (node (ref "U2") (pin "22") (pinfunction "P7.3_22") (pintype "passive"))
    )
    (net (code "79") (name "unconnected-(U2-P7.4-Pad23)") (class "Default")
      (node (ref "U2") (pin "23") (pinfunction "P7.4_23") (pintype "passive"))
    )
    (net (code "80") (name "unconnected-(U4-NR{slash}FB-Pad4)") (class "Default")
      (node (ref "U4") (pin "4") (pinfunction "NR/FB_4") (pintype "passive"))
    )
    (net (code "81") (name "unconnected-(U5-NR{slash}FB-Pad4)") (class "Default")
      (node (ref "U5") (pin "4") (pinfunction "NR/FB_4") (pintype "passive"))
    )
    (net (code "82") (name "unconnected-(U8-CBUS0-Pad23)") (class "Default")
      (node (ref "U8") (pin "23") (pinfunction "CBUS0_23") (pintype "passive"))
    )
    (net (code "83") (name "unconnected-(U8-CBUS1-Pad22)") (class "Default")
      (node (ref "U8") (pin "22") (pinfunction "CBUS1_22") (pintype "passive"))
    )
    (net (code "84") (name "unconnected-(U8-CBUS2-Pad13)") (class "Default")
      (node (ref "U8") (pin "13") (pinfunction "CBUS2_13") (pintype "passive"))
    )
    (net (code "85") (name "unconnected-(U8-CBUS3-Pad14)") (class "Default")
      (node (ref "U8") (pin "14") (pinfunction "CBUS3_14") (pintype "passive"))
    )
    (net (code "86") (name "unconnected-(U8-CBUS4-Pad12)") (class "Default")
      (node (ref "U8") (pin "12") (pinfunction "CBUS4_12") (pintype "passive"))
    )
    (net (code "87") (name "unconnected-(U8-NC-Pad8)") (class "Default")
      (node (ref "U8") (pin "8") (pinfunction "NC_8") (pintype "passive"))
    )
    (net (code "88") (name "unconnected-(U8-NC-Pad24)") (class "Default")
      (node (ref "U8") (pin "24") (pinfunction "NC_24") (pintype "passive"))
    )
    (net (code "89") (name "unconnected-(U8-OSCI-Pad27)") (class "Default")
      (node (ref "U8") (pin "27") (pinfunction "OSCI_27") (pintype "passive"))
    )
    (net (code "90") (name "unconnected-(U8-OSCO-Pad28)") (class "Default")
      (node (ref "U8") (pin "28") (pinfunction "OSCO_28") (pintype "passive"))
    )
    (net (code "91") (name "unconnected-(U8-~{DCD}-Pad10)") (class "Default")
      (node (ref "U8") (pin "10") (pinfunction "~{DCD}_10") (pintype "passive"))
    )
    (net (code "92") (name "unconnected-(U8-~{DSR}-Pad9)") (class "Default")
      (node (ref "U8") (pin "9") (pinfunction "~{DSR}_9") (pintype "passive"))
    )
    (net (code "93") (name "unconnected-(U8-~{DTR}-Pad2)") (class "Default")
      (node (ref "U8") (pin "2") (pinfunction "~{DTR}_2") (pintype "passive"))
    )
    (net (code "94") (name "unconnected-(U8-~{RESET}-Pad19)") (class "Default")
      (node (ref "U8") (pin "19") (pinfunction "~{RESET}_19") (pintype "passive"))
    )
    (net (code "95") (name "unconnected-(U8-~{RI}-Pad6)") (class "Default")
      (node (ref "U8") (pin "6") (pinfunction "~{RI}_6") (pintype "passive"))
    )
    (net (code "96") (name "unconnected-(U8-~{RTS}-Pad3)") (class "Default")
      (node (ref "U8") (pin "3") (pinfunction "~{RTS}_3") (pintype "passive"))
    )
    (net (code "97") (name "unconnected-(U9-DAT1-Pad8)") (class "Default")
      (node (ref "U9") (pin "8") (pinfunction "DAT1_8") (pintype "passive"))
    )
    (net (code "98") (name "unconnected-(U9-DAT2-Pad1)") (class "Default")
      (node (ref "U9") (pin "1") (pinfunction "DAT2_1") (pintype "passive"))
    )
  )
)
